# Strobe.net
KiCad netlist of a schematic drawn in Altium Designer
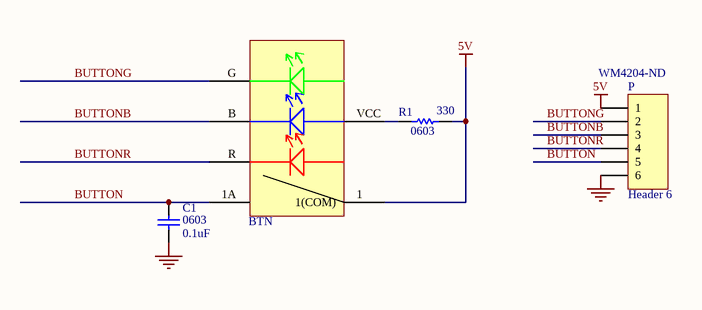
[diagram p0: Strobe.SchDoc]

(export (version "E")
  (design (tool "Eeschema 10.0.6"))
  (components
    (comp (ref "BTN")
      (value "KP0115ANBKG03RGB-2SJB")
      (footprint "KP0115ANBKG03RGB-2SJB")
      (description "Pushbutton Switch SPST-NO Standard, Illuminated Through Hole")
      (libsource (lib "Schlib") (part "KP0115ANBKG03RGB-2SJB"))
    )
    (comp (ref "C1")
      (value "0603")
      (footprint "C0603")
      (description "CAP CER 0.1UF 50V X5R 0603")
      (fields (field (name "ALTIUM_VALUE") "0.1uF") (field (name "TOLERANCE") "10%"))
      (libsource (lib "Miscellaneous Devices") (part "Cap"))
    )
    (comp (ref "P")
      (value "Header 6")
      (footprint "Molex HDR1X6")
      (description "CONN HEADER VERT 6POS 2.54MM")
      (fields (field (name "SUPPLIER PART NUMBER 1") "WM4204-ND") (field (name "PUBLISHER") "Altium Limited"))
      (libsource (lib "Miscellaneous Connectors") (part "Header 6"))
    )
    (comp (ref "R1")
      (value "0603")
      (footprint "R0603")
      (description "RES SMD 330 OHM 1% 1/10W 0603")
      (fields (field (name "ALTIUM_VALUE") "330") (field (name "TOLERANCE") "1%"))
      (libsource (lib "Miscellaneous Devices") (part "Res1"))
    )
  )
  (nets
    (net (code "1") (name "/BUTTON") (class "Default")
      (node (ref "BTN") (pin "1A") (pinfunction "1A_1A") (pintype "passive"))
      (node (ref "C1") (pin "2") (pinfunction "2_2") (pintype "passive"))
      (node (ref "P") (pin "5") (pinfunction "5_5") (pintype "passive"))
    )
    (net (code "2") (name "/BUTTONB") (class "Default")
      (node (ref "BTN") (pin "B") (pinfunction "B(-)_B") (pintype "passive"))
      (node (ref "P") (pin "3") (pinfunction "3_3") (pintype "passive"))
    )
    (net (code "3") (name "/BUTTONG") (class "Default")
      (node (ref "BTN") (pin "G") (pinfunction "G(-)_G") (pintype "passive"))
      (node (ref "P") (pin "2") (pinfunction "2_2") (pintype "passive"))
    )
    (net (code "4") (name "/BUTTONR") (class "Default")
      (node (ref "BTN") (pin "R") (pinfunction "R(-)_R") (pintype "passive"))
      (node (ref "P") (pin "4") (pinfunction "4_4") (pintype "passive"))
    )
    (net (code "5") (name "5V") (class "Default")
      (node (ref "BTN") (pin "1") (pinfunction "1(COM)_1") (pintype "passive"))
      (node (ref "P") (pin "1") (pinfunction "1_1") (pintype "passive"))
      (node (ref "R1") (pin "2") (pinfunction "2_2") (pintype "passive"))
    )
    (net (code "6") (name "GND") (class "Default")
      (node (ref "C1") (pin "1") (pinfunction "1_1") (pintype "passive"))
      (node (ref "P") (pin "6") (pinfunction "6_6") (pintype "passive"))
    )
    (net (code "7") (name "Net-(BTN-3V3)") (class "Default")
      (node (ref "BTN") (pin "VCC") (pinfunction "3V3_VCC") (pintype "passive"))
      (node (ref "R1") (pin "1") (pinfunction "1_1") (pintype "passive"))
    )
  )
)
